# HeatMapNodeV1.net
KiCad netlist of a schematic drawn in Altium Designer
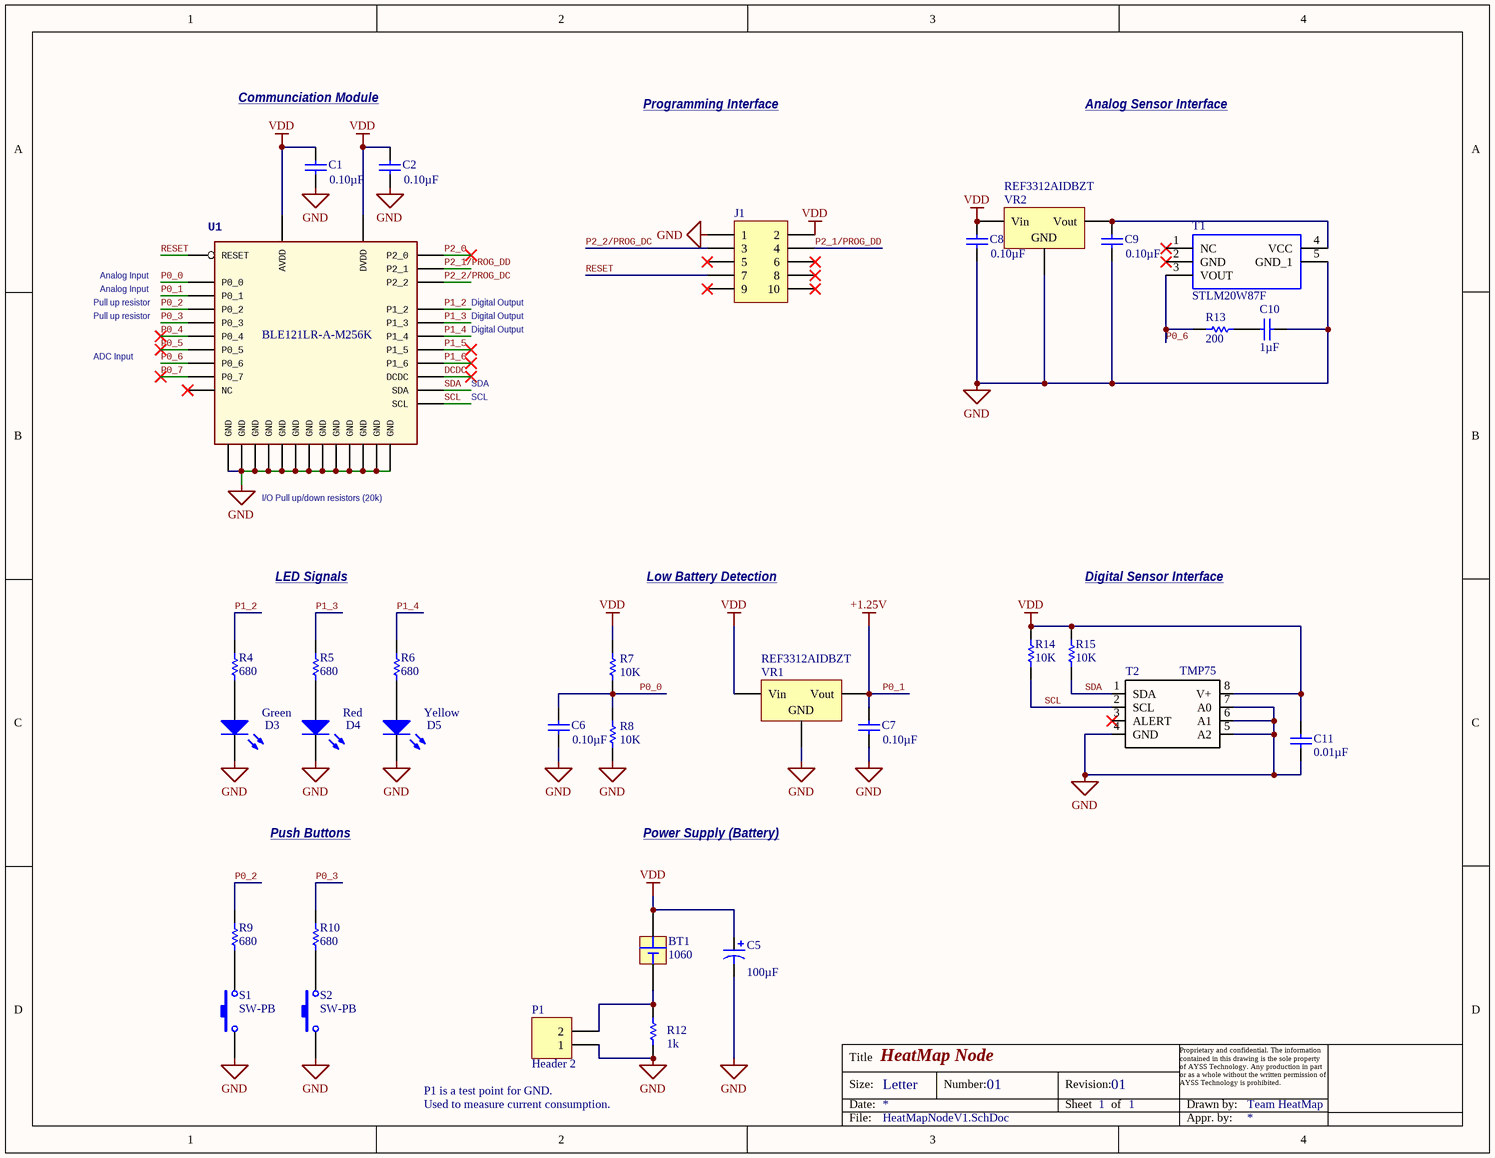
[diagram p0: HeatMapNodeV1.SchDoc]

(export (version "E")
  (design (tool "Eeschema 10.0.6"))
  (components
    (comp (ref "BT1")
      (value "1060")
      (footprint "1060")
      (description "Coin Cell Battery 2032 Holder")
      (fields (field (name "MANUFACTURER") "Keystone Electronics"))
      (libsource (lib "Keystone_1057") (part "Battery"))
    )
    (comp (ref "C1")
      (value "0.10µF")
      (footprint "6-0805_M")
      (description "Capacitor (Semiconductor SIM Model)")
      (fields
        (field (name "MANUFACTURER") "Taiyo Yuden")
        (field (name "MANUFACTURER PART NUMBER") "HMK212B7104KG-T")
        (field (name "PUBLISHER") "Altium Limited")
      )
      (libsource (lib "Miscellaneous Devices") (part "Cap Semi"))
    )
    (comp (ref "C2")
      (value "0.10µF")
      (footprint "6-0805_M")
      (description "Capacitor (Semiconductor SIM Model)")
      (fields
        (field (name "MANUFACTURER") "Taiyo Yuden")
        (field (name "MANUFACTURER PART NUMBER") "HMK212B7104KG-T")
        (field (name "PUBLISHER") "Altium Limited")
      )
      (libsource (lib "Miscellaneous Devices") (part "Cap Semi"))
    )
    (comp (ref "C5")
      (value "100µF")
      (footprint "D")
      (description "Polarized Capacitor (Surface Mount)")
      (fields
        (field (name "MANUFACTURER") "KEMET")
        (field (name "MANUFACTURER PART NUMBER") "T495D107K016ATE125")
        (field (name "PUBLISHER") "Altium Limited")
      )
      (libsource (lib "Miscellaneous Devices") (part "Cap Pol3"))
    )
    (comp (ref "C6")
      (value "0.10µF")
      (footprint "6-0805_M")
      (description "Capacitor (Semiconductor SIM Model)")
      (fields
        (field (name "MANUFACTURER") "Taiyo Yuden")
        (field (name "MANUFACTURER PART NUMBER") "HMK212B7104KG-T")
        (field (name "PUBLISHER") "Altium Limited")
      )
      (libsource (lib "Miscellaneous Devices") (part "Cap Semi"))
    )
    (comp (ref "C7")
      (value "0.10µF")
      (footprint "6-0805_M")
      (description "Capacitor (Semiconductor SIM Model)")
      (fields
        (field (name "MANUFACTURER") "Taiyo Yuden")
        (field (name "MANUFACTURER PART NUMBER") "HMK212B7104KG-T")
        (field (name "PUBLISHER") "Altium Limited")
      )
      (libsource (lib "Miscellaneous Devices") (part "Cap Semi"))
    )
    (comp (ref "C8")
      (value "0.10µF")
      (footprint "6-0805_M")
      (description "Capacitor (Semiconductor SIM Model)")
      (fields
        (field (name "MANUFACTURER") "Taiyo Yuden")
        (field (name "MANUFACTURER PART NUMBER") "HMK212B7104KG-T")
        (field (name "PUBLISHER") "Altium Limited")
      )
      (libsource (lib "Miscellaneous Devices") (part "Cap Semi"))
    )
    (comp (ref "C9")
      (value "0.10µF")
      (footprint "6-0805_M")
      (description "Capacitor (Semiconductor SIM Model)")
      (fields
        (field (name "MANUFACTURER") "Taiyo Yuden")
        (field (name "MANUFACTURER PART NUMBER") "HMK212B7104KG-T")
        (field (name "PUBLISHER") "Altium Limited")
      )
      (libsource (lib "Miscellaneous Devices") (part "Cap Semi"))
    )
    (comp (ref "C10")
      (value "1µF")
      (footprint "6-0805_M")
      (description "Capacitor (Semiconductor SIM Model)")
      (fields
        (field (name "MANUFACTURER") "Taiyo Yuden")
        (field (name "MANUFACTURER PART NUMBER") "HMK212B7104KG-T")
        (field (name "PUBLISHER") "Altium Limited")
      )
      (libsource (lib "Miscellaneous Devices") (part "Cap Semi"))
    )
    (comp (ref "C11")
      (value "0.01µF")
      (footprint "6-0805_M")
      (description "Capacitor (Semiconductor SIM Model)")
      (fields
        (field (name "MANUFACTURER") "Taiyo Yuden")
        (field (name "MANUFACTURER PART NUMBER") "HMK212B7104KG-T")
        (field (name "PUBLISHER") "Altium Limited")
      )
      (libsource (lib "Miscellaneous Devices") (part "Cap Semi"))
    )
    (comp (ref "D3")
      (value "LED2")
      (footprint "2.0X1.25X1.2")
      (description "Typical RED, GREEN, YELLOW, AMBER GaAs LED")
      (fields
        (field (name "MANUFACTURER") "Visual Communications Company - VCC")
        (field (name "MANUFACTURER PART NUMBER") "CMD17-21VGD/TR8")
        (field (name "COLOR") "Green")
      )
      (libsource (lib "Miscellaneous Devices") (part "LED2"))
    )
    (comp (ref "D4")
      (value "LED2")
      (footprint "2.0X1.25X1.2")
      (description "Typical RED, GREEN, YELLOW, AMBER GaAs LED")
      (fields
        (field (name "MANUFACTURER") "Visual Communications Company - VCC")
        (field (name "MANUFACTURER PART NUMBER") "CMD17-21VRD/TR8")
        (field (name "COLOR") "Red")
      )
      (libsource (lib "Miscellaneous Devices") (part "LED2"))
    )
    (comp (ref "D5")
      (value "LED2")
      (footprint "2.0X1.25X1.2")
      (description "Typical RED, GREEN, YELLOW, AMBER GaAs LED")
      (fields
        (field (name "MANUFACTURER") "Visual Communications Company - VCC")
        (field (name "MANUFACTURER PART NUMBER") "CMD17-21VYD/TR8")
        (field (name "COLOR") "Yellow")
      )
      (libsource (lib "Miscellaneous Devices") (part "LED2"))
    )
    (comp (ref "J1")
      (value "Header 5X2")
      (footprint "HDR2X5_SMD_127")
      (description "Header, 5-Pin, Dual row")
      (fields
        (field (name "MANUFACTURER") "Amphenol FCI")
        (field (name "MANUFACTURER PART NUMBER") "20021521-00010T1LF")
        (field (name "PUBLISHER") "Altium Limited")
      )
      (libsource (lib "Miscellaneous Connectors") (part "Header 5X2"))
    )
    (comp (ref "P1")
      (value "Header 2")
      (footprint "HDR1X2")
      (description "Header, 2-Pin")
      (libsource (lib "Miscellaneous Connectors") (part "Header 2"))
    )
    (comp (ref "R4")
      (value "680")
      (footprint "6-0805_M")
      (description "Resistor")
      (fields
        (field (name "MANUFACTURER") "Vishay Dale")
        (field (name "MANUFACTURER PART NUMBER") "CRCW0805680RFKEA")
      )
      (libsource (lib "Miscellaneous Devices") (part "Res1"))
    )
    (comp (ref "R5")
      (value "680")
      (footprint "6-0805_M")
      (description "Resistor")
      (fields
        (field (name "MANUFACTURER") "Vishay Dale")
        (field (name "MANUFACTURER PART NUMBER") "CRCW0805680RFKEA")
      )
      (libsource (lib "Miscellaneous Devices") (part "Res1"))
    )
    (comp (ref "R6")
      (value "680")
      (footprint "6-0805_M")
      (description "Resistor")
      (fields
        (field (name "MANUFACTURER") "Vishay Dale")
        (field (name "MANUFACTURER PART NUMBER") "CRCW0805680RFKEA")
      )
      (libsource (lib "Miscellaneous Devices") (part "Res1"))
    )
    (comp (ref "R7")
      (value "10K")
      (footprint "6-0805_M")
      (description "Resistor")
      (fields
        (field (name "MANUFACTURER") "Vishay Dale")
        (field (name "MANUFACTURER PART NUMBER") "CRCW080510K0FKEA")
      )
      (libsource (lib "Miscellaneous Devices") (part "Res1"))
    )
    (comp (ref "R8")
      (value "10K")
      (footprint "6-0805_M")
      (description "Resistor")
      (fields
        (field (name "MANUFACTURER") "Vishay Dale")
        (field (name "MANUFACTURER PART NUMBER") "CRCW080510K0FKEA")
      )
      (libsource (lib "Miscellaneous Devices") (part "Res1"))
    )
    (comp (ref "R9")
      (value "680")
      (footprint "6-0805_M")
      (description "Resistor")
      (fields
        (field (name "MANUFACTURER") "Vishay Dale")
        (field (name "MANUFACTURER PART NUMBER") "CRCW0805680RFKEA")
      )
      (libsource (lib "Miscellaneous Devices") (part "Res1"))
    )
    (comp (ref "R10")
      (value "680")
      (footprint "6-0805_M")
      (description "Resistor")
      (fields
        (field (name "MANUFACTURER") "Vishay Dale")
        (field (name "MANUFACTURER PART NUMBER") "CRCW0805680RFKEA")
      )
      (libsource (lib "Miscellaneous Devices") (part "Res1"))
    )
    (comp (ref "R12")
      (value "1k")
      (footprint "6-0805_M")
      (description "Resistor")
      (fields
        (field (name "MANUFACTURER") "Vishay Dale")
        (field (name "MANUFACTURER PART NUMBER") "CRCW08050000Z0EA")
      )
      (libsource (lib "Miscellaneous Devices") (part "Res1"))
    )
    (comp (ref "R13")
      (value "200")
      (footprint "6-0805_M")
      (description "Resistor")
      (fields
        (field (name "MANUFACTURER") "Vishay Dale")
        (field (name "MANUFACTURER PART NUMBER") "CRCW0805680RFKEA")
      )
      (libsource (lib "Miscellaneous Devices") (part "Res1"))
    )
    (comp (ref "R14")
      (value "10K")
      (footprint "6-0805_M")
      (description "Resistor")
      (fields
        (field (name "MANUFACTURER") "Vishay Dale")
        (field (name "MANUFACTURER PART NUMBER") "CRCW0805680RFKEA")
      )
      (libsource (lib "Miscellaneous Devices") (part "Res1"))
    )
    (comp (ref "R15")
      (value "10K")
      (footprint "6-0805_M")
      (description "Resistor")
      (fields
        (field (name "MANUFACTURER") "Vishay Dale")
        (field (name "MANUFACTURER PART NUMBER") "CRCW0805680RFKEA")
      )
      (libsource (lib "Miscellaneous Devices") (part "Res1"))
    )
    (comp (ref "S1")
      (value "SW-PB")
      (footprint "SPST-2")
      (description "Switch")
      (fields (field (name "PUBLISHER") "Altium Limited"))
      (libsource (lib "Miscellaneous Devices") (part "SW-PB"))
    )
    (comp (ref "S2")
      (value "SW-PB")
      (footprint "SPST-2")
      (description "Switch")
      (fields (field (name "PUBLISHER") "Altium Limited"))
      (libsource (lib "Miscellaneous Devices") (part "SW-PB"))
    )
    (comp (ref "T1")
      (value "STLM20W87F")
      (footprint "SOT65P210X110-5N")
      (description "STLM20W87F, Temperature Sensor 1.5C 2.4 to 5.5V 5-Pin SOT-323")
      (fields (field (name "RS PART NUMBER") "1685835"))
      (libsource (lib "STLM20W87F") (part "STLM20W87F"))
    )
    (comp (ref "T2")
      (value "TMP75")
      (footprint "MSOP8")
      (fields (field (name "MF") "Texas Instruments"))
      (libsource (lib "TMP75") (part "TMP75"))
    )
    (comp (ref "U1")
      (value "BLE121LR module")
      (footprint "BLE121LR")
      (description "Bluetooth Low Energy (BLE) module")
      (fields
        (field (name "MANUFACTURER") "Silicon Labs")
        (field (name "MANUFACTURER PART NUMBER") "BLE121LR-A-M256K")
      )
      (libsource (lib "BLE121LR") (part "BLE121LR"))
    )
    (comp (ref "VR1")
      (value "Volt Reg")
      (footprint "SOT23_M")
      (description "Voltage Regulator")
      (fields
        (field (name "MANUFACTURER") "Texas Instruments")
        (field (name "MANUFACTURER PART NUMBER") "REF3312AIDBZT")
        (field (name "TOLERANCE") "±0.15%")
      )
      (libsource (lib "Miscellaneous Devices") (part "Volt Reg"))
    )
    (comp (ref "VR2")
      (value "Volt Reg")
      (footprint "SOT23_M")
      (description "Voltage Regulator")
      (fields
        (field (name "MANUFACTURER") "Texas Instruments")
        (field (name "MANUFACTURER PART NUMBER") "REF3312AIDBZT")
        (field (name "TOLERANCE") "±0.15%")
      )
      (libsource (lib "Miscellaneous Devices") (part "Volt Reg"))
    )
  )
  (nets
    (net (code "1") (name "+1.25V") (class "Default")
      (node (ref "C7") (pin "2") (pinfunction "2_2") (pintype "passive"))
      (node (ref "U1") (pin "5") (pinfunction "P0_1_5") (pintype "passive"))
      (node (ref "VR1") (pin "3") (pinfunction "Vout_3") (pintype "passive"))
    )
    (net (code "2") (name "/DCDC") (class "Default")
      (node (ref "U1") (pin "18") (pinfunction "DCDC_18") (pintype "passive+no_connect"))
    )
    (net (code "3") (name "/P0_0") (class "Default")
      (node (ref "C6") (pin "2") (pinfunction "2_2") (pintype "passive"))
      (node (ref "R7") (pin "1") (pinfunction "1_1") (pintype "passive"))
      (node (ref "R8") (pin "2") (pinfunction "2_2") (pintype "passive"))
      (node (ref "U1") (pin "6") (pinfunction "P0_0_6") (pintype "passive"))
    )
    (net (code "4") (name "/P0_2") (class "Default")
      (node (ref "R9") (pin "1") (pinfunction "1_1") (pintype "passive"))
      (node (ref "U1") (pin "4") (pinfunction "P0_2_4") (pintype "passive"))
    )
    (net (code "5") (name "/P0_3") (class "Default")
      (node (ref "R10") (pin "1") (pinfunction "1_1") (pintype "passive"))
      (node (ref "U1") (pin "8") (pinfunction "P0_3_8") (pintype "passive"))
    )
    (net (code "6") (name "/P0_4") (class "Default")
      (node (ref "U1") (pin "9") (pinfunction "P0_4_9") (pintype "passive+no_connect"))
    )
    (net (code "7") (name "/P0_5") (class "Default")
      (node (ref "U1") (pin "10") (pinfunction "P0_5_10") (pintype "passive+no_connect"))
    )
    (net (code "8") (name "/P0_6") (class "Default")
      (node (ref "R13") (pin "1") (pinfunction "1_1") (pintype "passive"))
      (node (ref "T1") (pin "3") (pinfunction "VOUT_3") (pintype "passive"))
      (node (ref "U1") (pin "11") (pinfunction "P0_6_11") (pintype "passive"))
    )
    (net (code "9") (name "/P0_7") (class "Default")
      (node (ref "U1") (pin "12") (pinfunction "P0_7_12") (pintype "passive+no_connect"))
    )
    (net (code "10") (name "/P1_2") (class "Default")
      (node (ref "R4") (pin "1") (pinfunction "1_1") (pintype "passive"))
      (node (ref "U1") (pin "30") (pinfunction "P1_2_30") (pintype "passive"))
    )
    (net (code "11") (name "/P1_3") (class "Default")
      (node (ref "R5") (pin "1") (pinfunction "1_1") (pintype "passive"))
      (node (ref "U1") (pin "29") (pinfunction "P1_3_29") (pintype "passive"))
    )
    (net (code "12") (name "/P1_4") (class "Default")
      (node (ref "R6") (pin "1") (pinfunction "1_1") (pintype "passive"))
      (node (ref "U1") (pin "28") (pinfunction "P1_4_28") (pintype "passive"))
    )
    (net (code "13") (name "/P1_5") (class "Default")
      (node (ref "U1") (pin "27") (pinfunction "P1_5_27") (pintype "passive+no_connect"))
    )
    (net (code "14") (name "/P1_6") (class "Default")
      (node (ref "U1") (pin "17") (pinfunction "P1_6_17") (pintype "passive+no_connect"))
    )
    (net (code "15") (name "/P2_0") (class "Default")
      (node (ref "U1") (pin "19") (pinfunction "P2_0_19") (pintype "passive+no_connect"))
    )
    (net (code "16") (name "/P2_1{slash}PROG_DD") (class "Default")
      (node (ref "J1") (pin "4") (pinfunction "4_4") (pintype "passive"))
      (node (ref "U1") (pin "20") (pinfunction "P2_1_20") (pintype "passive"))
    )
    (net (code "17") (name "/P2_2{slash}PROG_DC") (class "Default")
      (node (ref "J1") (pin "3") (pinfunction "3_3") (pintype "passive"))
      (node (ref "U1") (pin "21") (pinfunction "P2_2_21") (pintype "passive"))
    )
    (net (code "18") (name "/RESET") (class "Default")
      (node (ref "J1") (pin "7") (pinfunction "7_7") (pintype "passive"))
      (node (ref "U1") (pin "7") (pinfunction "RESET_7") (pintype "passive"))
    )
    (net (code "19") (name "/SCL") (class "Default")
      (node (ref "R14") (pin "2") (pinfunction "2_2") (pintype "passive"))
      (node (ref "T2") (pin "2") (pinfunction "SCL_2") (pintype "bidirectional"))
      (node (ref "U1") (pin "24") (pinfunction "SCL_24") (pintype "passive"))
    )
    (net (code "20") (name "/SDA") (class "Default")
      (node (ref "R15") (pin "2") (pinfunction "2_2") (pintype "passive"))
      (node (ref "T2") (pin "1") (pinfunction "SDA_1") (pintype "bidirectional"))
      (node (ref "U1") (pin "25") (pinfunction "SDA_25") (pintype "passive"))
    )
    (net (code "21") (name "GND") (class "Default")
      (node (ref "C1") (pin "1") (pinfunction "1_1") (pintype "passive"))
      (node (ref "C10") (pin "1") (pinfunction "1_1") (pintype "passive"))
      (node (ref "C11") (pin "1") (pinfunction "1_1") (pintype "passive"))
      (node (ref "C2") (pin "1") (pinfunction "1_1") (pintype "passive"))
      (node (ref "C5") (pin "2") (pinfunction "2_2") (pintype "passive"))
      (node (ref "C6") (pin "1") (pinfunction "1_1") (pintype "passive"))
      (node (ref "C7") (pin "1") (pinfunction "1_1") (pintype "passive"))
      (node (ref "C8") (pin "1") (pinfunction "1_1") (pintype "passive"))
      (node (ref "C9") (pin "1") (pinfunction "1_1") (pintype "passive"))
      (node (ref "D3") (pin "2") (pinfunction "K_2") (pintype "passive"))
      (node (ref "D4") (pin "2") (pinfunction "K_2") (pintype "passive"))
      (node (ref "D5") (pin "2") (pinfunction "K_2") (pintype "passive"))
      (node (ref "J1") (pin "1") (pinfunction "1_1") (pintype "passive"))
      (node (ref "P1") (pin "1") (pinfunction "1_1") (pintype "passive"))
      (node (ref "R12") (pin "2") (pinfunction "2_2") (pintype "passive"))
      (node (ref "R8") (pin "1") (pinfunction "1_1") (pintype "passive"))
      (node (ref "S1") (pin "1") (pinfunction "1_1") (pintype "passive"))
      (node (ref "S2") (pin "1") (pinfunction "1_1") (pintype "passive"))
      (node (ref "T1") (pin "5") (pinfunction "GND_1_5") (pintype "passive"))
      (node (ref "T2") (pin "4") (pinfunction "GND_4") (pintype "bidirectional"))
      (node (ref "T2") (pin "5") (pinfunction "A2_5") (pintype "bidirectional"))
      (node (ref "T2") (pin "6") (pinfunction "A1_6") (pintype "bidirectional"))
      (node (ref "T2") (pin "7") (pinfunction "A0_7") (pintype "bidirectional"))
      (node (ref "U1") (pin "1") (pinfunction "GND_1") (pintype "power_in"))
      (node (ref "U1") (pin "14") (pinfunction "GND_14") (pintype "power_in"))
      (node (ref "U1") (pin "15") (pinfunction "GND_15") (pintype "power_in"))
      (node (ref "U1") (pin "16") (pinfunction "GND_16") (pintype "power_in"))
      (node (ref "U1") (pin "2") (pinfunction "GND_2") (pintype "power_in"))
      (node (ref "U1") (pin "22") (pinfunction "GND_22") (pintype "power_in"))
      (node (ref "U1") (pin "3") (pinfunction "GND_3") (pintype "power_in"))
      (node (ref "U1") (pin "31") (pinfunction "GND_31") (pintype "power_in"))
      (node (ref "U1") (pin "32") (pinfunction "GND_32") (pintype "power_in"))
      (node (ref "U1") (pin "33") (pinfunction "GND_33") (pintype "power_in"))
      (node (ref "U1") (pin "34") (pinfunction "GND_34") (pintype "power_in"))
      (node (ref "U1") (pin "35") (pinfunction "GND_35") (pintype "power_in"))
      (node (ref "U1") (pin "36") (pinfunction "GND_36") (pintype "power_in"))
      (node (ref "VR1") (pin "2") (pinfunction "GND_2") (pintype "passive"))
      (node (ref "VR2") (pin "2") (pinfunction "GND_2") (pintype "passive"))
    )
    (net (code "22") (name "Net-(BT1--)") (class "Default")
      (node (ref "BT1") (pin "1") (pinfunction "-_1") (pintype "passive"))
      (node (ref "P1") (pin "2") (pinfunction "2_2") (pintype "passive"))
      (node (ref "R12") (pin "1") (pinfunction "1_1") (pintype "passive"))
    )
    (net (code "23") (name "Net-(C10-Pad2)") (class "Default")
      (node (ref "C10") (pin "2") (pinfunction "2_2") (pintype "passive"))
      (node (ref "R13") (pin "2") (pinfunction "2_2") (pintype "passive"))
    )
    (net (code "24") (name "Net-(D3-A)") (class "Default")
      (node (ref "D3") (pin "1") (pinfunction "A_1") (pintype "passive"))
      (node (ref "R4") (pin "2") (pinfunction "2_2") (pintype "passive"))
    )
    (net (code "25") (name "Net-(D4-A)") (class "Default")
      (node (ref "D4") (pin "1") (pinfunction "A_1") (pintype "passive"))
      (node (ref "R5") (pin "2") (pinfunction "2_2") (pintype "passive"))
    )
    (net (code "26") (name "Net-(D5-A)") (class "Default")
      (node (ref "D5") (pin "1") (pinfunction "A_1") (pintype "passive"))
      (node (ref "R6") (pin "2") (pinfunction "2_2") (pintype "passive"))
    )
    (net (code "27") (name "Net-(R9-Pad2)") (class "Default")
      (node (ref "R9") (pin "2") (pinfunction "2_2") (pintype "passive"))
      (node (ref "S1") (pin "2") (pinfunction "2_2") (pintype "passive"))
    )
    (net (code "28") (name "Net-(R10-Pad2)") (class "Default")
      (node (ref "R10") (pin "2") (pinfunction "2_2") (pintype "passive"))
      (node (ref "S2") (pin "2") (pinfunction "2_2") (pintype "passive"))
    )
    (net (code "29") (name "Net-(T1-VCC)") (class "Default")
      (node (ref "C9") (pin "2") (pinfunction "2_2") (pintype "passive"))
      (node (ref "T1") (pin "4") (pinfunction "VCC_4") (pintype "power_in"))
      (node (ref "VR2") (pin "3") (pinfunction "Vout_3") (pintype "passive"))
    )
    (net (code "30") (name "VDD") (class "Default")
      (node (ref "BT1") (pin "2") (pinfunction "+_2") (pintype "passive"))
      (node (ref "C1") (pin "2") (pinfunction "2_2") (pintype "passive"))
      (node (ref "C11") (pin "2") (pinfunction "2_2") (pintype "passive"))
      (node (ref "C2") (pin "2") (pinfunction "2_2") (pintype "passive"))
      (node (ref "C5") (pin "1") (pinfunction "1_1") (pintype "passive"))
      (node (ref "C8") (pin "2") (pinfunction "2_2") (pintype "passive"))
      (node (ref "J1") (pin "2") (pinfunction "2_2") (pintype "passive"))
      (node (ref "R14") (pin "1") (pinfunction "1_1") (pintype "passive"))
      (node (ref "R15") (pin "1") (pinfunction "1_1") (pintype "passive"))
      (node (ref "R7") (pin "2") (pinfunction "2_2") (pintype "passive"))
      (node (ref "T2") (pin "8") (pinfunction "V+_8") (pintype "bidirectional"))
      (node (ref "U1") (pin "13") (pinfunction "AVDD_13") (pintype "power_in"))
      (node (ref "U1") (pin "23") (pinfunction "DVDD_23") (pintype "power_in"))
      (node (ref "VR1") (pin "1") (pinfunction "Vin_1") (pintype "passive"))
      (node (ref "VR2") (pin "1") (pinfunction "Vin_1") (pintype "passive"))
    )
    (net (code "31") (name "unconnected-(J1-Pad5)") (class "Default")
      (node (ref "J1") (pin "5") (pinfunction "5_5") (pintype "passive+no_connect"))
    )
    (net (code "32") (name "unconnected-(J1-Pad6)") (class "Default")
      (node (ref "J1") (pin "6") (pinfunction "6_6") (pintype "passive+no_connect"))
    )
    (net (code "33") (name "unconnected-(J1-Pad8)") (class "Default")
      (node (ref "J1") (pin "8") (pinfunction "8_8") (pintype "passive+no_connect"))
    )
    (net (code "34") (name "unconnected-(J1-Pad9)") (class "Default")
      (node (ref "J1") (pin "9") (pinfunction "9_9") (pintype "passive+no_connect"))
    )
    (net (code "35") (name "unconnected-(J1-Pad10)") (class "Default")
      (node (ref "J1") (pin "10") (pinfunction "10_10") (pintype "passive+no_connect"))
    )
    (net (code "36") (name "unconnected-(T1-GND-Pad2)") (class "Default")
      (node (ref "T1") (pin "2") (pinfunction "GND_2") (pintype "passive+no_connect"))
    )
    (net (code "37") (name "unconnected-(T1-NC-Pad1)") (class "Default")
      (node (ref "T1") (pin "1") (pinfunction "NC_1") (pintype "passive+no_connect"))
    )
    (net (code "38") (name "unconnected-(T2-ALERT-Pad3)") (class "Default")
      (node (ref "T2") (pin "3") (pinfunction "ALERT_3") (pintype "bidirectional+no_connect"))
    )
    (net (code "39") (name "unconnected-(U1-NC-Pad26)") (class "Default")
      (node (ref "U1") (pin "26") (pinfunction "NC_26") (pintype "passive+no_connect"))
    )
  )
)
